# Hamilton.net
KiCad netlist of a schematic drawn in Altium Designer
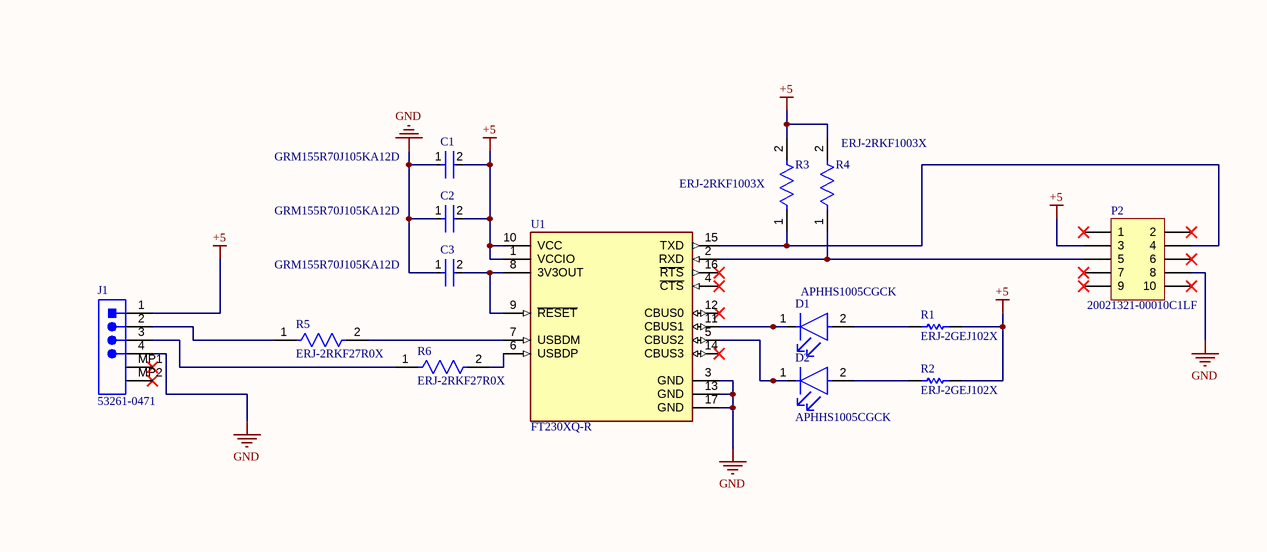
[diagram p0: Hamilton.SchDoc, right]

(export (version "E")
  (design (tool "Eeschema 10.0.6"))
  (components
    (comp (ref "C1")
      (value "GRM155R70J105KA12D")
      (footprint "FP-GRM155-0_05-MFG")
      (description "Chip Multilayer Ceramic Capacitors for General Purpose, 0402, 1.0uF, X7R, 15%, 10%, 6.3V")
      (fields (field (name "TOLERANCE") "10%"))
      (libsource (lib "Altium Content Vault") (part "02cd4be3c70576c341d710602a673aa"))
    )
    (comp (ref "C2")
      (value "GRM155R70J105KA12D")
      (footprint "FP-GRM155-0_05-MFG")
      (description "Chip Multilayer Ceramic Capacitors for General Purpose, 0402, 1.0uF, X7R, 15%, 10%, 6.3V")
      (fields (field (name "TOLERANCE") "10%"))
      (libsource (lib "Altium Content Vault") (part "02cd4be3c70576c341d710602a673aa"))
    )
    (comp (ref "C3")
      (value "GRM155R70J105KA12D")
      (footprint "FP-GRM155-0_05-MFG")
      (description "Chip Multilayer Ceramic Capacitors for General Purpose, 0402, 1.0uF, X7R, 15%, 10%, 6.3V")
      (fields (field (name "TOLERANCE") "10%"))
      (libsource (lib "Altium Content Vault") (part "02cd4be3c70576c341d710602a673aa"))
    )
    (comp (ref "D1")
      (value "APHHS1005CGCK")
      (footprint "FP-APHHS1005CGCK-MFG")
      (description "LED GREEN CLEAR CHIP SMD")
      (libsource (lib "Altium Content Vault") (part "8706943c75ba83719d021d2fdc84c58"))
    )
    (comp (ref "D2")
      (value "APHHS1005CGCK")
      (footprint "FP-APHHS1005CGCK-MFG")
      (description "LED GREEN CLEAR CHIP SMD")
      (libsource (lib "Altium Content Vault") (part "8706943c75ba83719d021d2fdc84c58"))
    )
    (comp (ref "J1")
      (value "53261-0471")
      (footprint "MOLEX-53261-0471_V")
      (description "Male Header, Pitch 1.25 mm, 1 x 4 Position, Height 3.4 mm, -40 to 85 degC, RoHS, Tape and Reel")
      (fields (field (name "MANUFACTURER") "Molex"))
      (libsource (lib "Altium Content Vault") (part "CN-1P-2M-R4_A"))
    )
    (comp (ref "P2")
      (value "20021321-00010C1LF")
      (footprint "PCBComponent_1")
      (description "Header, 5-Pin, Dual row")
      (fields (field (name "PUBLISHER") "Altium Limited"))
      (libsource (lib "Miscellaneous Connectors") (part "Header 5X2"))
    )
    (comp (ref "R1")
      (value "ERJ-2GEJ102X")
      (footprint "RESC1005X40X25NL05T05")
      (fields (field (name "MANUFACTURER") "Panasonic"))
      (libsource (lib "Altium Content Vault") (part "RES"))
    )
    (comp (ref "R2")
      (value "ERJ-2GEJ102X")
      (footprint "RESC1005X40X25NL05T05")
      (fields (field (name "MANUFACTURER") "Panasonic"))
      (libsource (lib "Altium Content Vault") (part "RES"))
    )
    (comp (ref "R3")
      (value "ERJ-2RKF1003X")
      (footprint "FP-ERJ2RK-IPC_C")
      (description "RES SMD 100K OHM 1% 1/10W 0402")
      (fields (field (name "TOLERANCE") "1%"))
      (libsource (lib "Altium Content Vault") (part "1029c3af85768c4190bb7ad29bc67b5"))
    )
    (comp (ref "R4")
      (value "ERJ-2RKF1003X")
      (footprint "FP-ERJ2RK-IPC_C")
      (description "RES SMD 100K OHM 1% 1/10W 0402")
      (fields (field (name "TOLERANCE") "1%"))
      (libsource (lib "Altium Content Vault") (part "1029c3af85768c4190bb7ad29bc67b5"))
    )
    (comp (ref "R5")
      (value "ERJ-2RKF27R0X")
      (footprint "FP-ERJ2R-IPC_B")
      (description "RES SMD 27 OHM 1% 1/10W 0402")
      (fields (field (name "TOLERANCE") "1%"))
      (libsource (lib "Altium Content Vault") (part "8db39607336c341a927600551d01821"))
    )
    (comp (ref "R6")
      (value "ERJ-2RKF27R0X")
      (footprint "FP-ERJ2R-IPC_B")
      (description "RES SMD 27 OHM 1% 1/10W 0402")
      (fields (field (name "TOLERANCE") "1%"))
      (libsource (lib "Altium Content Vault") (part "8db39607336c341a927600551d01821"))
    )
    (comp (ref "U1")
      (value "FT230XQ-R")
      (footprint "FP-QFN-16-MFG")
      (description "IC USB SERIAL BASIC UART 16QFN")
      (libsource (lib "Altium Content Vault") (part "29d2eb9587eff32afae5da052de4085"))
    )
  )
  (nets
    (net (code "1") (name "+5") (class "Default")
      (node (ref "C1") (pin "2") (pinfunction "2_2") (pintype "passive"))
      (node (ref "C2") (pin "2") (pinfunction "2_2") (pintype "passive"))
      (node (ref "J1") (pin "1") (pinfunction "1_1") (pintype "passive"))
      (node (ref "P2") (pin "3") (pinfunction "3_3") (pintype "passive"))
      (node (ref "R1") (pin "2") (pinfunction "2_2") (pintype "passive"))
      (node (ref "R2") (pin "2") (pinfunction "2_2") (pintype "passive"))
      (node (ref "R3") (pin "2") (pinfunction "2_2") (pintype "passive"))
      (node (ref "R4") (pin "2") (pinfunction "2_2") (pintype "passive"))
      (node (ref "U1") (pin "1") (pinfunction "VCCIO_1") (pintype "power_in"))
      (node (ref "U1") (pin "10") (pinfunction "VCC_10") (pintype "power_in"))
    )
    (net (code "2") (name "GND") (class "Default")
      (node (ref "C1") (pin "1") (pinfunction "1_1") (pintype "passive"))
      (node (ref "C2") (pin "1") (pinfunction "1_1") (pintype "passive"))
      (node (ref "C3") (pin "1") (pinfunction "1_1") (pintype "passive"))
      (node (ref "J1") (pin "4") (pinfunction "4_4") (pintype "passive"))
      (node (ref "P2") (pin "8") (pinfunction "8_8") (pintype "passive"))
      (node (ref "U1") (pin "13") (pinfunction "GND_13") (pintype "power_in"))
      (node (ref "U1") (pin "17") (pinfunction "GND_17") (pintype "power_in"))
      (node (ref "U1") (pin "3") (pinfunction "GND_3") (pintype "power_in"))
    )
    (net (code "3") (name "Net-(D1-A)") (class "Default")
      (node (ref "D1") (pin "2") (pinfunction "A_2") (pintype "passive"))
      (node (ref "R1") (pin "1") (pinfunction "1_1") (pintype "passive"))
    )
    (net (code "4") (name "Net-(D1-C)") (class "Default")
      (node (ref "D1") (pin "1") (pinfunction "C_1") (pintype "passive"))
      (node (ref "U1") (pin "11") (pinfunction "CBUS1_11") (pintype "bidirectional"))
    )
    (net (code "5") (name "Net-(D2-A)") (class "Default")
      (node (ref "D2") (pin "2") (pinfunction "A_2") (pintype "passive"))
      (node (ref "R2") (pin "1") (pinfunction "1_1") (pintype "passive"))
    )
    (net (code "6") (name "Net-(D2-C)") (class "Default")
      (node (ref "D2") (pin "1") (pinfunction "C_1") (pintype "passive"))
      (node (ref "U1") (pin "5") (pinfunction "CBUS2_5") (pintype "bidirectional"))
    )
    (net (code "7") (name "Net-(J1-Pad2)") (class "Default")
      (node (ref "J1") (pin "2") (pinfunction "2_2") (pintype "passive"))
      (node (ref "R5") (pin "1") (pinfunction "1_1") (pintype "passive"))
    )
    (net (code "8") (name "Net-(J1-Pad3)") (class "Default")
      (node (ref "J1") (pin "3") (pinfunction "3_3") (pintype "passive"))
      (node (ref "R6") (pin "1") (pinfunction "1_1") (pintype "passive"))
    )
    (net (code "9") (name "Net-(U1-3V3OUT)") (class "Default")
      (node (ref "C3") (pin "2") (pinfunction "2_2") (pintype "passive"))
      (node (ref "U1") (pin "8") (pinfunction "3V3OUT_8") (pintype "power_in"))
      (node (ref "U1") (pin "9") (pinfunction "~{RESET}_9") (pintype "input"))
    )
    (net (code "10") (name "Net-(U1-RXD)") (class "Default")
      (node (ref "P2") (pin "5") (pinfunction "5_5") (pintype "passive"))
      (node (ref "R4") (pin "1") (pinfunction "1_1") (pintype "passive"))
      (node (ref "U1") (pin "2") (pinfunction "RXD_2") (pintype "input"))
    )
    (net (code "11") (name "Net-(U1-TXD)") (class "Default")
      (node (ref "P2") (pin "4") (pinfunction "4_4") (pintype "passive"))
      (node (ref "R3") (pin "1") (pinfunction "1_1") (pintype "passive"))
      (node (ref "U1") (pin "15") (pinfunction "TXD_15") (pintype "output"))
    )
    (net (code "12") (name "Net-(U1-USBDM)") (class "Default")
      (node (ref "R5") (pin "2") (pinfunction "2_2") (pintype "passive"))
      (node (ref "U1") (pin "7") (pinfunction "USBDM_7") (pintype "input"))
    )
    (net (code "13") (name "Net-(U1-USBDP)") (class "Default")
      (node (ref "R6") (pin "2") (pinfunction "2_2") (pintype "passive"))
      (node (ref "U1") (pin "6") (pinfunction "USBDP_6") (pintype "input"))
    )
    (net (code "14") (name "unconnected-(J1-PadMP1)") (class "Default")
      (node (ref "J1") (pin "MP1") (pinfunction "MP1_MP1") (pintype "passive+no_connect"))
    )
    (net (code "15") (name "unconnected-(J1-PadMP2)") (class "Default")
      (node (ref "J1") (pin "MP2") (pinfunction "MP2_MP2") (pintype "passive+no_connect"))
    )
    (net (code "16") (name "unconnected-(P2-Pad1)") (class "Default")
      (node (ref "P2") (pin "1") (pinfunction "1_1") (pintype "passive+no_connect"))
    )
    (net (code "17") (name "unconnected-(P2-Pad2)") (class "Default")
      (node (ref "P2") (pin "2") (pinfunction "2_2") (pintype "passive+no_connect"))
    )
    (net (code "18") (name "unconnected-(P2-Pad6)") (class "Default")
      (node (ref "P2") (pin "6") (pinfunction "6_6") (pintype "passive+no_connect"))
    )
    (net (code "19") (name "unconnected-(P2-Pad7)") (class "Default")
      (node (ref "P2") (pin "7") (pinfunction "7_7") (pintype "passive+no_connect"))
    )
    (net (code "20") (name "unconnected-(P2-Pad9)") (class "Default")
      (node (ref "P2") (pin "9") (pinfunction "9_9") (pintype "passive+no_connect"))
    )
    (net (code "21") (name "unconnected-(P2-Pad10)") (class "Default")
      (node (ref "P2") (pin "10") (pinfunction "10_10") (pintype "passive+no_connect"))
    )
    (net (code "22") (name "unconnected-(U1-CBUS0-Pad12)") (class "Default")
      (node (ref "U1") (pin "12") (pinfunction "CBUS0_12") (pintype "bidirectional+no_connect"))
    )
    (net (code "23") (name "unconnected-(U1-CBUS3-Pad14)") (class "Default")
      (node (ref "U1") (pin "14") (pinfunction "CBUS3_14") (pintype "bidirectional+no_connect"))
    )
    (net (code "24") (name "unconnected-(U1-~{CTS}-Pad4)") (class "Default")
      (node (ref "U1") (pin "4") (pinfunction "~{CTS}_4") (pintype "input+no_connect"))
    )
    (net (code "25") (name "unconnected-(U1-~{RTS}-Pad16)") (class "Default")
      (node (ref "U1") (pin "16") (pinfunction "~{RTS}_16") (pintype "output+no_connect"))
    )
  )
)
